# V_BACKUP.net
KiCad netlist of a schematic drawn in Altium Designer
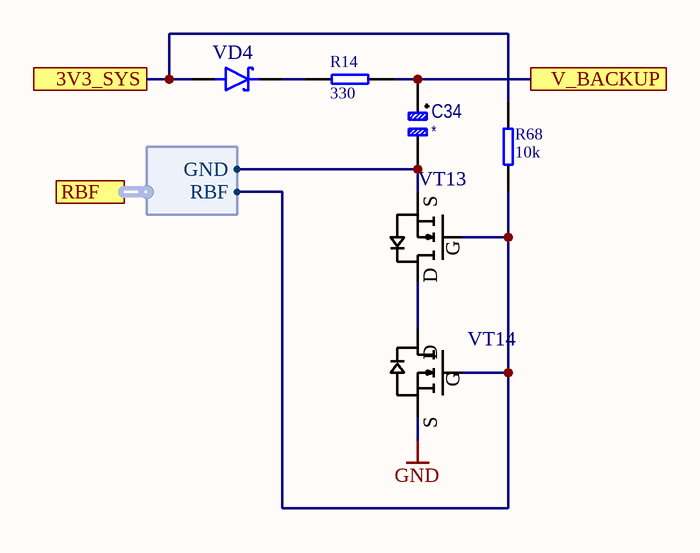
[diagram p0: V_BACKUP.SchDoc]

(export (version "E")
  (design (tool "Eeschema 10.0.6"))
  (components
    (comp (ref "C34")
      (value "*")
      (footprint "DCS5R5224H")
      (description "Super Capacitor")
      (fields (field (name "ALTIUM_VALUE") "*"))
      (libsource (lib "!main") (part "Ionistor"))
    )
    (comp (ref "R14")
      (value "330")
      (footprint "RES 0402")
      (description "Resistor")
      (fields (field (name "Comment") "RES 0402 330"))
      (libsource (lib "!main") (part "!Resistor"))
    )
    (comp (ref "R68")
      (value "10k")
      (footprint "RES 0402")
      (description "Resistor")
      (fields (field (name "Comment") "RES 0402 10k"))
      (libsource (lib "!main") (part "!Resistor"))
    )
    (comp (ref "VD4")
      (value "Shottly diode SOD-123")
      (footprint "SOD-123")
      (description "Diode Shottky")
      (libsource (lib "diodes") (part "DiodeS"))
    )
    (comp (ref "VT13")
      (value "2N7002")
      (footprint "SOT23-3")
      (description "generic N mosfet")
      (libsource (lib "transistors") (part "!Generic N MOSFET"))
    )
    (comp (ref "VT14")
      (value "2N7002")
      (footprint "SOT23-3")
      (description "generic N mosfet")
      (libsource (lib "transistors") (part "!Generic N MOSFET"))
    )
  )
  (nets
    (net (code "2") (name "/3V3_SYS") (class "Default")
      (node (ref "R68") (pin "2") (pinfunction "12_2") (pintype "passive"))
      (node (ref "VD4") (pin "A") (pinfunction "Anode_A") (pintype "passive"))
    )
    (net (code "3") (name "/V_BACKUP") (class "Default")
      (node (ref "C34") (pin "1") (pinfunction "+_1") (pintype "power_in"))
      (node (ref "R14") (pin "2") (pinfunction "12_2") (pintype "passive"))
    )
    (net (code "5") (name "GND") (class "Default") (node (ref "VT14") (pin "S1") (pintype "passive")))
    (net (code "6") (name "Net-(C34--)") (class "Default")
      (node (ref "C34") (pin "2") (pinfunction "-_2") (pintype "power_in"))
      (node (ref "VT13") (pin "S1") (pintype "passive"))
    )
    (net (code "7") (name "Net-(R14-11)") (class "Default")
      (node (ref "R14") (pin "1") (pinfunction "11_1") (pintype "passive"))
      (node (ref "VD4") (pin "C") (pinfunction "Cathode_C") (pintype "passive"))
    )
    (net (code "8") (name "Net-(R68-11)") (class "Default")
      (node (ref "R68") (pin "1") (pinfunction "11_1") (pintype "passive"))
      (node (ref "VT13") (pin "G2") (pintype "passive"))
      (node (ref "VT14") (pin "G2") (pintype "passive"))
    )
    (net (code "9") (name "Net-(VT13-PadD6)") (class "Default")
      (node (ref "VT13") (pin "D6") (pintype "passive"))
      (node (ref "VT14") (pin "D6") (pintype "passive"))
    )
  )
)
